# Stabilizator.net
KiCad netlist of a schematic drawn in Altium Designer
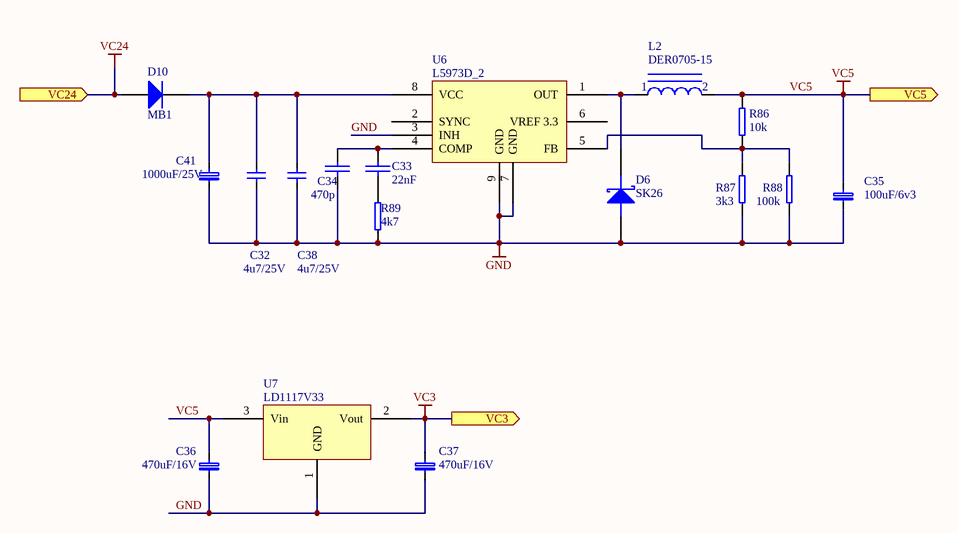
[diagram p0: Stabilizator.SchDoc]

(export (version "E")
  (design (tool "Eeschema 10.0.6"))
  (components
    (comp (ref "C32") (value "4u7/25V") (footprint "1206") (libsource (lib "") (part "CAP_1")))
    (comp (ref "C33")
      (value "22nF")
      (footprint "0805C")
      (description "Capacitor")
      (libsource (lib "*") (part "CAP"))
    )
    (comp (ref "C34")
      (value "470p")
      (footprint "0805C")
      (description "Capacitor")
      (libsource (lib "*") (part "CAP"))
    )
    (comp (ref "C35")
      (value "100uF/6v3")
      (footprint "CAP_C")
      (description "KONDENSATOR ELEKTROLITYCZNY TANTALOWY SMD")
      (libsource (lib "*") (part "CAP_TANTAL_SMD"))
    )
    (comp (ref "C36")
      (value "470uF/16V")
      (footprint "RB-.15/.30")
      (description "KONDENSATOR ELEKTROLITYCZNY TANTALOWY SMD")
      (libsource (lib "*") (part "CAP_TANTAL_SMD"))
    )
    (comp (ref "C37")
      (value "470uF/16V")
      (footprint "RB-.15/.30")
      (description "KONDENSATOR ELEKTROLITYCZNY TANTALOWY SMD")
      (libsource (lib "*") (part "CAP_TANTAL_SMD"))
    )
    (comp (ref "C38") (value "4u7/25V") (footprint "1206") (libsource (lib "") (part "CAP_1")))
    (comp (ref "C41")
      (value "1000uF/25V")
      (footprint "RB-.2/.4")
      (description "KONDENSATOR ELEKTROLITYCZNY TANTALOWY SMD")
      (libsource (lib "*") (part "CAP_TANTAL_SMD"))
    )
    (comp (ref "D6")
      (value "SK26")
      (footprint "RD5")
      (description "Schottky Diode")
      (libsource (lib "*") (part "DIODE SCHOTTKY"))
    )
    (comp (ref "D10")
      (value "MB1")
      (footprint "SMB")
      (description "Default Diode")
      (fields (field (name "PUBLISHER") "Altium Limited"))
      (libsource (lib "Miscellaneous Devices") (part "Diode"))
    )
    (comp (ref "L2") (value "DER0705-15") (footprint "DER0705_1") (libsource (lib "*") (part "CEWKA_1")))
    (comp (ref "R86") (value "10k") (footprint "0805R") (libsource (lib "*") (part "RES3")))
    (comp (ref "R87") (value "3k3") (footprint "0805R") (libsource (lib "*") (part "RES3")))
    (comp (ref "R88") (value "100k") (footprint "0805R") (libsource (lib "*") (part "RES3")))
    (comp (ref "R89") (value "4k7") (footprint "0805R") (libsource (lib "*") (part "RES3")))
    (comp (ref "U6") (value "L5973D_2") (footprint "SO8_M") (libsource (lib "ElhosSchLib") (part "L5973D_2")))
    (comp (ref "U7") (value "LD1117V33") (footprint "DPAK") (libsource (lib "*") (part "LD1117V33")))
  )
  (nets
    (net (code "1") (name "GND") (class "Default")
      (node (ref "C32") (pin "1") (pintype "passive"))
      (node (ref "C34") (pin "2") (pinfunction "2_2") (pintype "passive"))
      (node (ref "C35") (pin "1") (pintype "passive"))
      (node (ref "C36") (pin "1") (pintype "passive"))
      (node (ref "C37") (pin "1") (pintype "passive"))
      (node (ref "C38") (pin "1") (pintype "passive"))
      (node (ref "C41") (pin "1") (pintype "passive"))
      (node (ref "D6") (pin "A") (pinfunction "A_A") (pintype "passive"))
      (node (ref "R87") (pin "2") (pintype "passive"))
      (node (ref "R88") (pin "2") (pintype "passive"))
      (node (ref "R89") (pin "2") (pintype "passive"))
      (node (ref "U6") (pin "3") (pinfunction "INH_3") (pintype "passive"))
      (node (ref "U6") (pin "7") (pinfunction "GND_7") (pintype "passive"))
      (node (ref "U6") (pin "9") (pinfunction "GND_9") (pintype "passive"))
      (node (ref "U7") (pin "1") (pinfunction "GND_1") (pintype "passive"))
    )
    (net (code "2") (name "Net-(C33-Pad1)") (class "Default")
      (node (ref "C33") (pin "1") (pinfunction "1_1") (pintype "passive"))
      (node (ref "R89") (pin "1") (pintype "passive"))
    )
    (net (code "3") (name "Net-(U6-COMP)") (class "Default")
      (node (ref "C33") (pin "2") (pinfunction "2_2") (pintype "passive"))
      (node (ref "C34") (pin "1") (pinfunction "1_1") (pintype "passive"))
      (node (ref "U6") (pin "4") (pinfunction "COMP_4") (pintype "passive"))
    )
    (net (code "4") (name "Net-(U6-FB)") (class "Default")
      (node (ref "R86") (pin "2") (pintype "passive"))
      (node (ref "R87") (pin "1") (pintype "passive"))
      (node (ref "R88") (pin "1") (pintype "passive"))
      (node (ref "U6") (pin "5") (pinfunction "FB_5") (pintype "passive"))
    )
    (net (code "5") (name "Net-(U6-OUT)") (class "Default")
      (node (ref "D6") (pin "K") (pinfunction "K_K") (pintype "passive"))
      (node (ref "L2") (pin "1") (pintype "passive"))
      (node (ref "U6") (pin "1") (pinfunction "OUT_1") (pintype "passive"))
    )
    (net (code "6") (name "Net-(U6-VCC)") (class "Default")
      (node (ref "C32") (pin "2") (pintype "passive"))
      (node (ref "C38") (pin "2") (pintype "passive"))
      (node (ref "C41") (pin "2") (pintype "passive"))
      (node (ref "D10") (pin "K") (pinfunction "K_K") (pintype "passive"))
      (node (ref "U6") (pin "8") (pinfunction "VCC_8") (pintype "passive"))
    )
    (net (code "7") (name "VC3") (class "Default")
      (node (ref "C37") (pin "2") (pintype "passive"))
      (node (ref "U7") (pin "2") (pinfunction "Vout_2") (pintype "passive"))
    )
    (net (code "8") (name "VC5") (class "Default")
      (node (ref "C35") (pin "2") (pintype "passive"))
      (node (ref "C36") (pin "2") (pintype "passive"))
      (node (ref "L2") (pin "2") (pintype "passive"))
      (node (ref "R86") (pin "1") (pintype "passive"))
      (node (ref "U7") (pin "3") (pinfunction "Vin_3") (pintype "passive"))
    )
    (net (code "9") (name "VC24") (class "Default")
      (node (ref "D10") (pin "A") (pinfunction "A_A") (pintype "passive"))
    )
    (net (code "10") (name "unconnected-(U6-SYNC-Pad2)") (class "Default")
      (node (ref "U6") (pin "2") (pinfunction "SYNC_2") (pintype "passive"))
    )
    (net (code "11") (name "unconnected-(U6-VREF_3.3-Pad6)") (class "Default")
      (node (ref "U6") (pin "6") (pinfunction "VREF_3.3_6") (pintype "passive"))
    )
  )
)
